# harp_audio_switch_v1_0.net
KiCad netlist of a schematic drawn in EAGLE
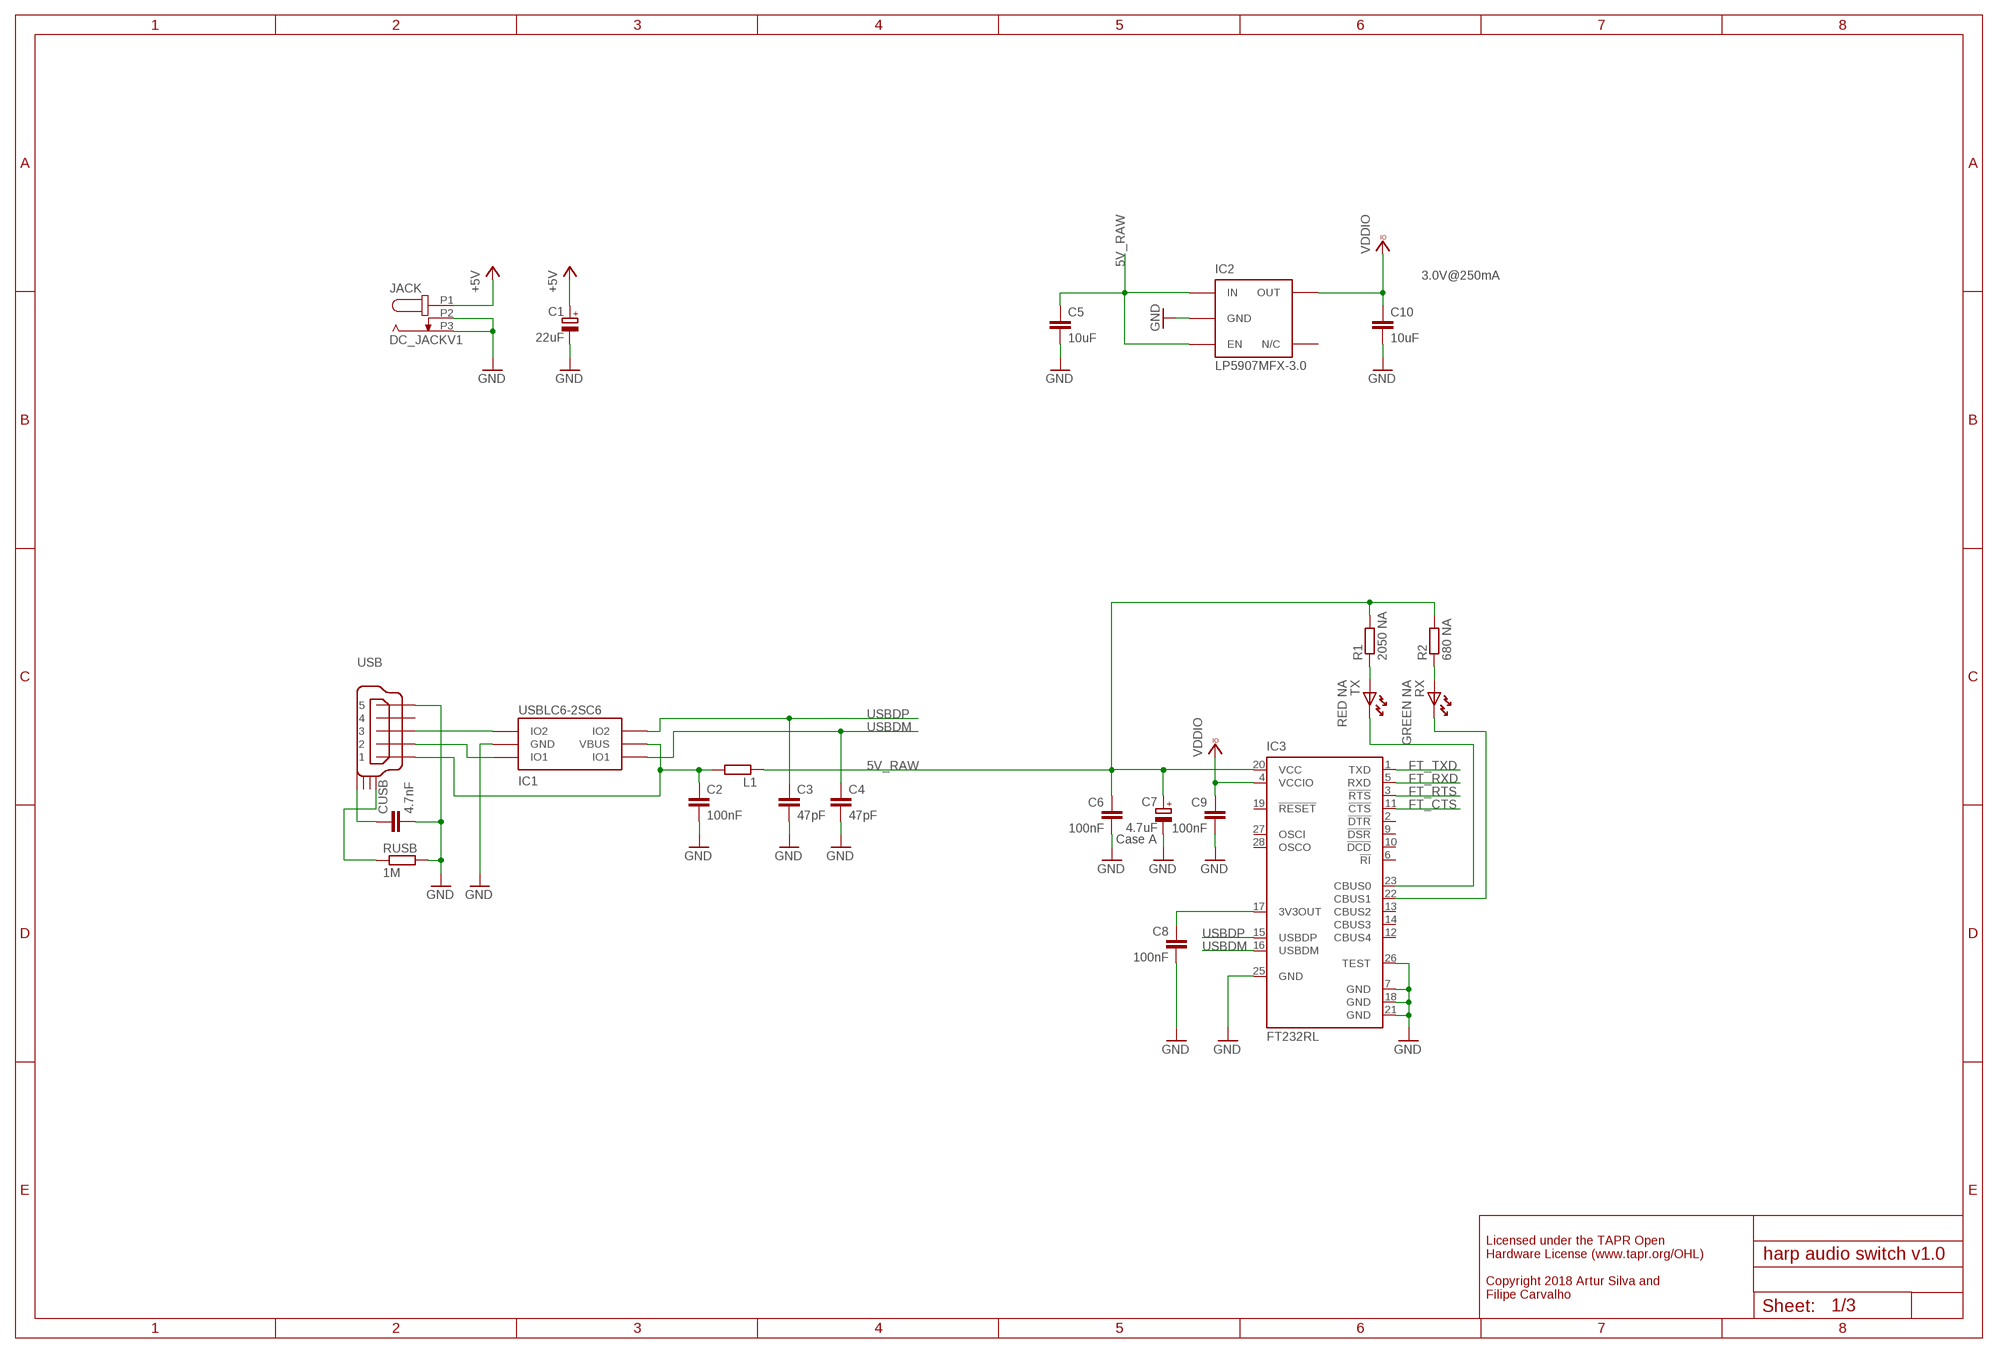
[diagram p0: schematic, sheet 1]
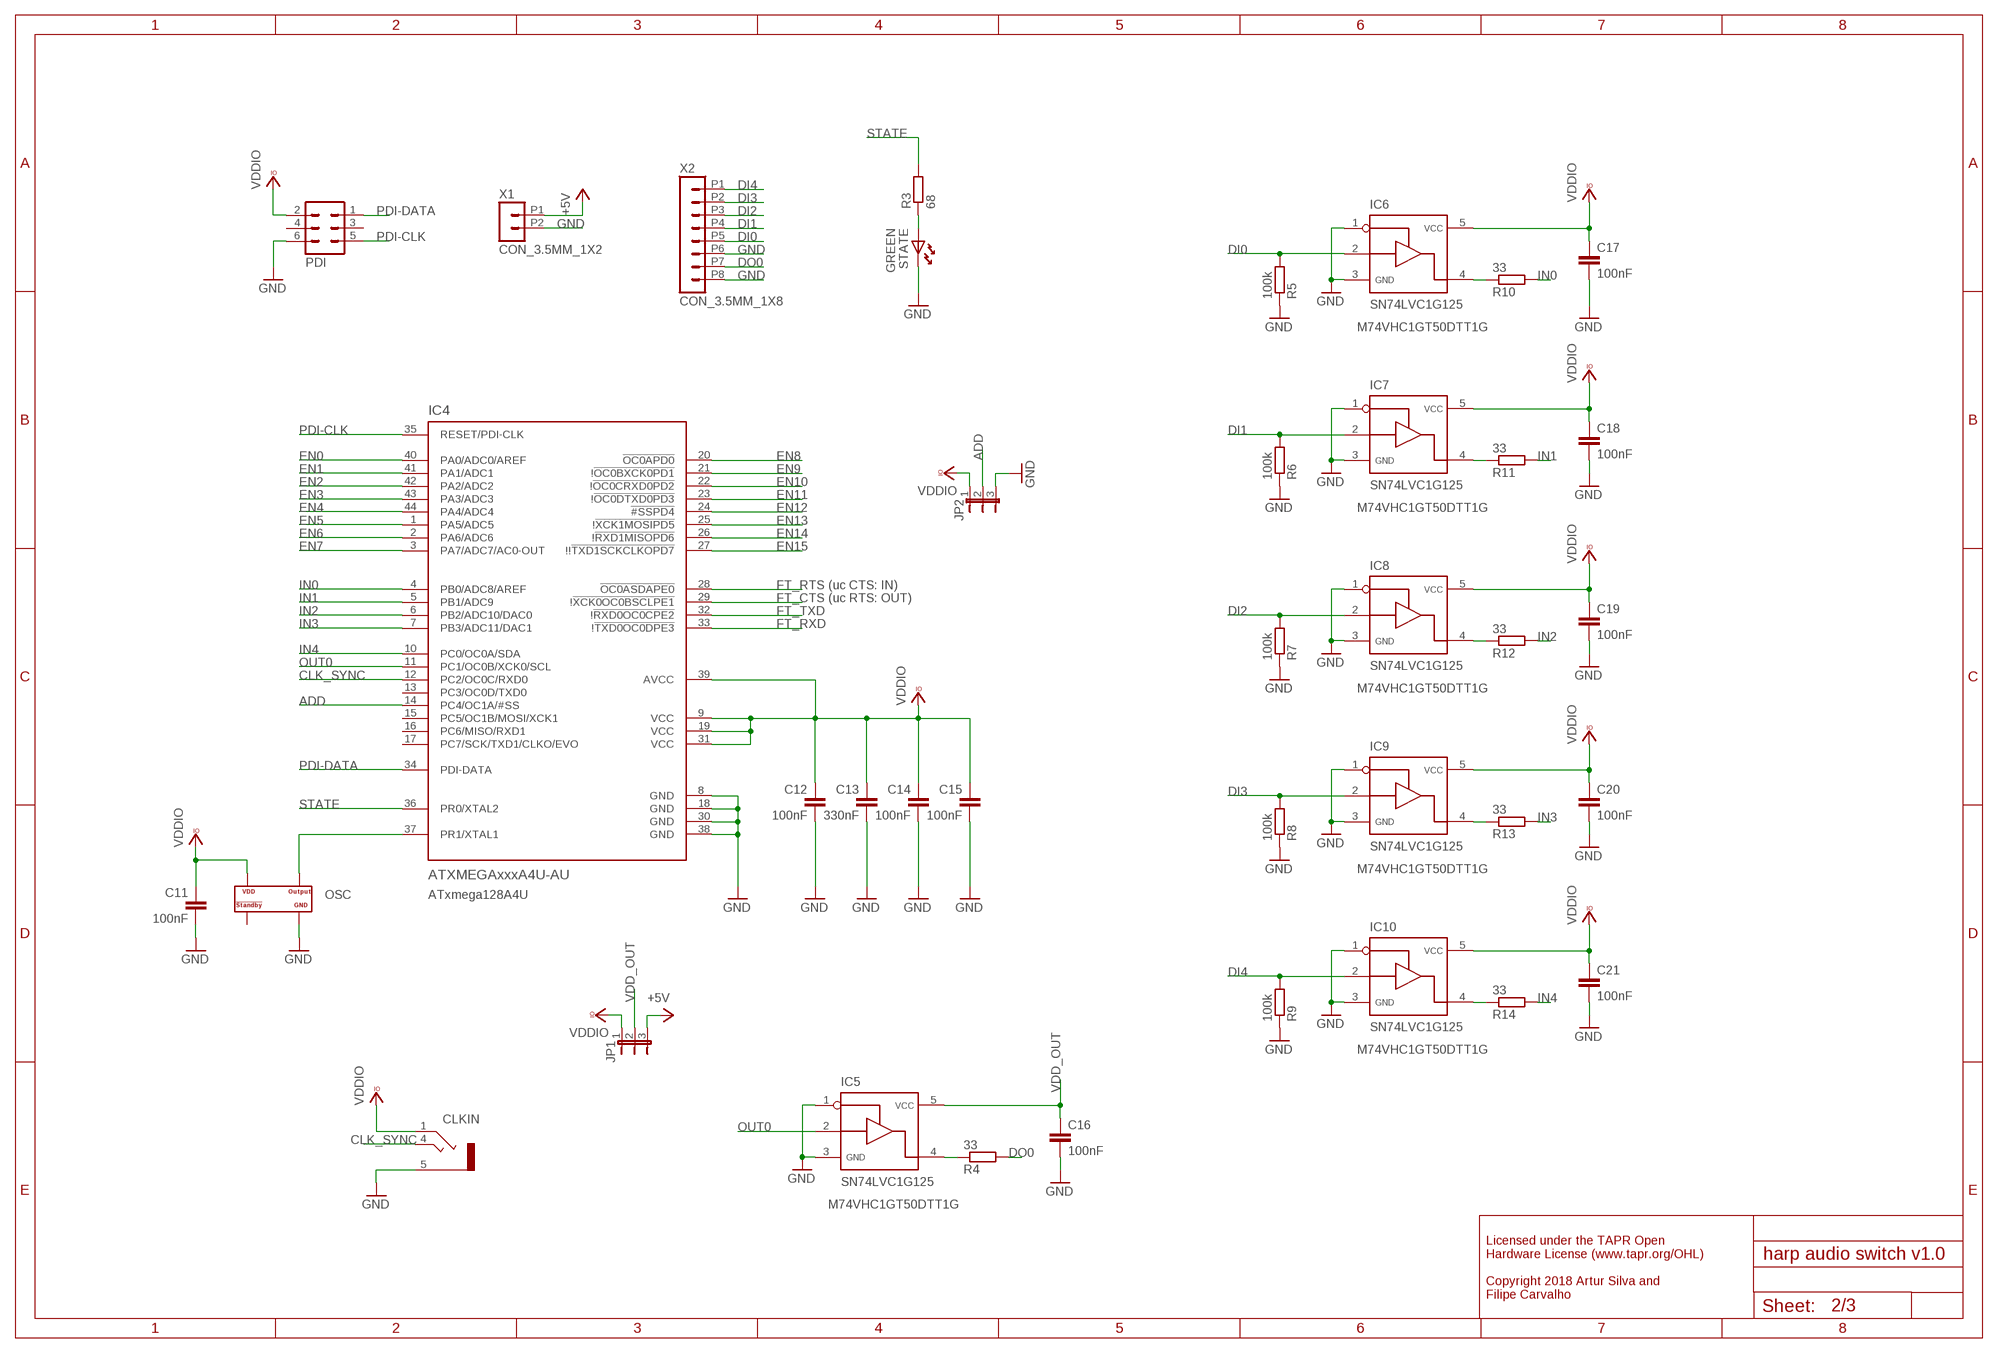
[diagram p1: schematic, sheet 2]
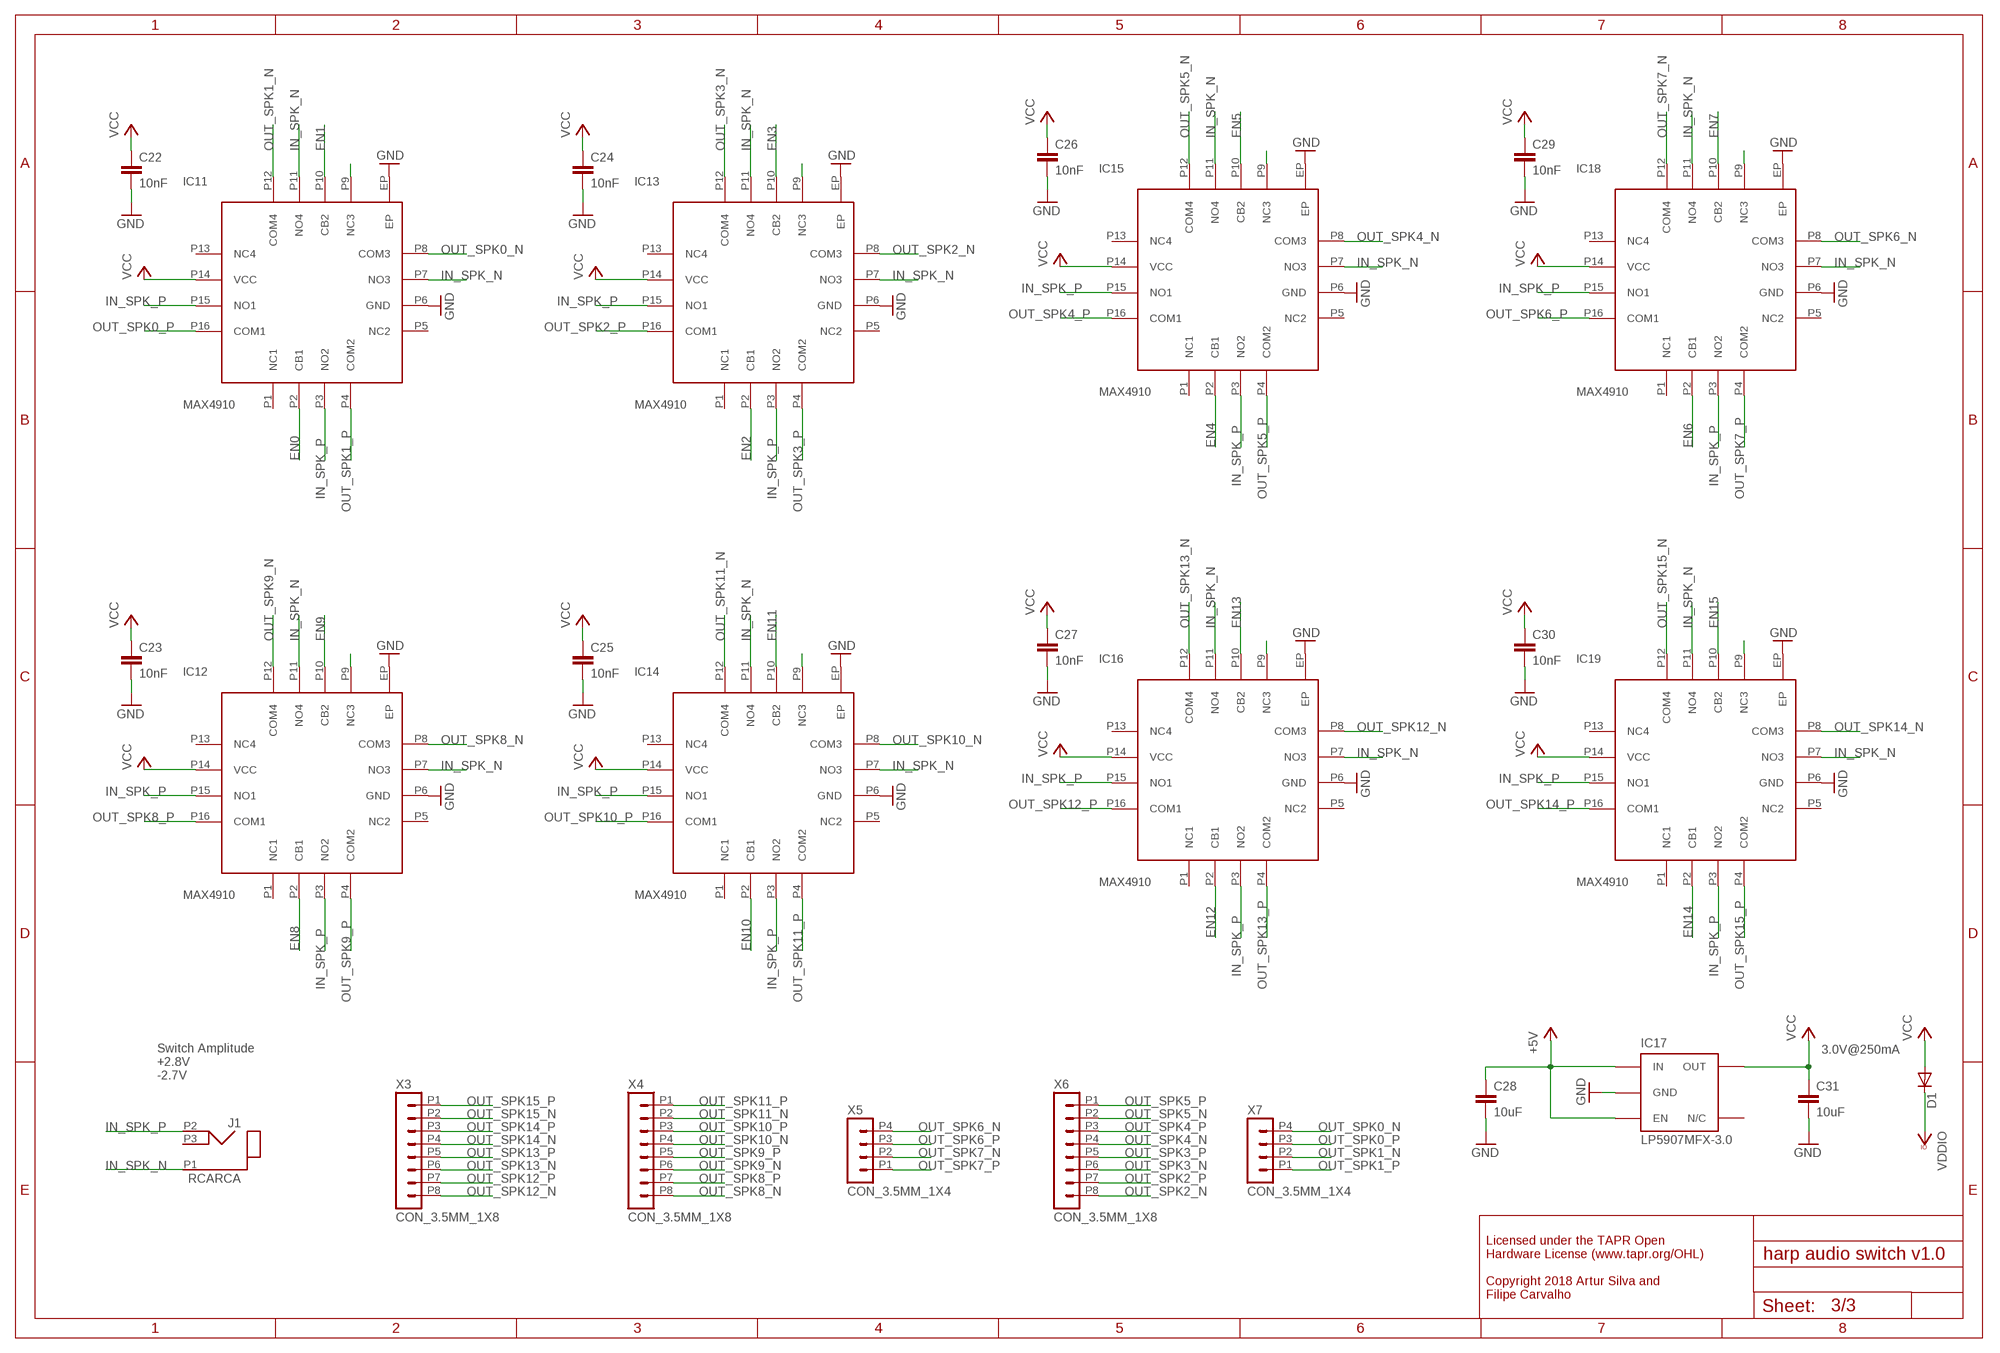
[diagram p2: schematic, sheet 3]

(export (version "E")
  (design (tool "Eeschema 10.0.6"))
  (components
    (comp (ref "C22")
      (value "10nF")
      (footprint "eagle-import:C0402")
      (libsource (lib "eagle-import") (part "C-EUC0402"))
    )
    (comp (ref "C23")
      (value "10nF")
      (footprint "eagle-import:C0402")
      (libsource (lib "eagle-import") (part "C-EUC0402"))
    )
    (comp (ref "C24")
      (value "10nF")
      (footprint "eagle-import:C0402")
      (libsource (lib "eagle-import") (part "C-EUC0402"))
    )
    (comp (ref "C25")
      (value "10nF")
      (footprint "eagle-import:C0402")
      (libsource (lib "eagle-import") (part "C-EUC0402"))
    )
    (comp (ref "C26")
      (value "10nF")
      (footprint "eagle-import:C0402")
      (libsource (lib "eagle-import") (part "C-EUC0402"))
    )
    (comp (ref "C27")
      (value "10nF")
      (footprint "eagle-import:C0402")
      (libsource (lib "eagle-import") (part "C-EUC0402"))
    )
    (comp (ref "C28")
      (value "10uF")
      (footprint "eagle-import:C0603")
      (libsource (lib "eagle-import") (part "C-EUC0603"))
    )
    (comp (ref "C29")
      (value "10nF")
      (footprint "eagle-import:C0402")
      (libsource (lib "eagle-import") (part "C-EUC0402"))
    )
    (comp (ref "C30")
      (value "10nF")
      (footprint "eagle-import:C0402")
      (libsource (lib "eagle-import") (part "C-EUC0402"))
    )
    (comp (ref "C31")
      (value "10uF")
      (footprint "eagle-import:C0603")
      (libsource (lib "eagle-import") (part "C-EUC0603"))
    )
    (comp (ref "D1")
      (value "DIODE-SOD323-R")
      (footprint "eagle-import:SOD323-R")
      (libsource (lib "eagle-import") (part "DIODE-SOD323-R"))
    )
    (comp (ref "IC11")
      (value "MAX4910")
      (footprint "eagle-import:QFN16")
      (libsource (lib "eagle-import") (part "MAX4910"))
    )
    (comp (ref "IC12")
      (value "MAX4910")
      (footprint "eagle-import:QFN16")
      (libsource (lib "eagle-import") (part "MAX4910"))
    )
    (comp (ref "IC13")
      (value "MAX4910")
      (footprint "eagle-import:QFN16")
      (libsource (lib "eagle-import") (part "MAX4910"))
    )
    (comp (ref "IC14")
      (value "MAX4910")
      (footprint "eagle-import:QFN16")
      (libsource (lib "eagle-import") (part "MAX4910"))
    )
    (comp (ref "IC15")
      (value "MAX4910")
      (footprint "eagle-import:QFN16")
      (libsource (lib "eagle-import") (part "MAX4910"))
    )
    (comp (ref "IC16")
      (value "MAX4910")
      (footprint "eagle-import:QFN16")
      (libsource (lib "eagle-import") (part "MAX4910"))
    )
    (comp (ref "IC17")
      (value "LP5907MFX-3.0")
      (footprint "eagle-import:TSOT23-5")
      (libsource (lib "eagle-import") (part "TLV700XX"))
    )
    (comp (ref "IC18")
      (value "MAX4910")
      (footprint "eagle-import:QFN16")
      (libsource (lib "eagle-import") (part "MAX4910"))
    )
    (comp (ref "IC19")
      (value "MAX4910")
      (footprint "eagle-import:QFN16")
      (libsource (lib "eagle-import") (part "MAX4910"))
    )
    (comp (ref "J1")
      (value "RCARCA")
      (footprint "eagle-import:RCA")
      (libsource (lib "eagle-import") (part "RCARCA"))
    )
    (comp (ref "X3")
      (value "CON_3.5MM_1X8")
      (footprint "eagle-import:CON_3.5MM_1X8")
      (libsource (lib "eagle-import") (part "CON_3.5MM_1X8"))
    )
    (comp (ref "X4")
      (value "CON_3.5MM_1X8")
      (footprint "eagle-import:CON_3.5MM_1X8")
      (libsource (lib "eagle-import") (part "CON_3.5MM_1X8"))
    )
    (comp (ref "X5")
      (value "CON_3.5MM_1X4")
      (footprint "eagle-import:CON_3.5MM_1X4")
      (libsource (lib "eagle-import") (part "CON_3.5MM_1X4"))
    )
    (comp (ref "X6")
      (value "CON_3.5MM_1X8")
      (footprint "eagle-import:CON_3.5MM_1X8")
      (libsource (lib "eagle-import") (part "CON_3.5MM_1X8"))
    )
    (comp (ref "X7")
      (value "CON_3.5MM_1X4")
      (footprint "eagle-import:CON_3.5MM_1X4")
      (libsource (lib "eagle-import") (part "CON_3.5MM_1X4"))
    )
    (comp (ref "C11")
      (value "100nF")
      (footprint "eagle-import:C0402")
      (libsource (lib "eagle-import") (part "C-EUC0402"))
    )
    (comp (ref "C12")
      (value "100nF")
      (footprint "eagle-import:C0402")
      (libsource (lib "eagle-import") (part "C-EUC0402"))
    )
    (comp (ref "C13")
      (value "330nF")
      (footprint "eagle-import:C0402")
      (libsource (lib "eagle-import") (part "C-EUC0402"))
    )
    (comp (ref "C14")
      (value "100nF")
      (footprint "eagle-import:C0402")
      (libsource (lib "eagle-import") (part "C-EUC0402"))
    )
    (comp (ref "C15")
      (value "100nF")
      (footprint "eagle-import:C0402")
      (libsource (lib "eagle-import") (part "C-EUC0402"))
    )
    (comp (ref "C16")
      (value "100nF")
      (footprint "eagle-import:C0402")
      (libsource (lib "eagle-import") (part "C-EUC0402"))
    )
    (comp (ref "C17")
      (value "100nF")
      (footprint "eagle-import:C0402")
      (libsource (lib "eagle-import") (part "C-EUC0402"))
    )
    (comp (ref "C18")
      (value "100nF")
      (footprint "eagle-import:C0402")
      (libsource (lib "eagle-import") (part "C-EUC0402"))
    )
    (comp (ref "C19")
      (value "100nF")
      (footprint "eagle-import:C0402")
      (libsource (lib "eagle-import") (part "C-EUC0402"))
    )
    (comp (ref "C20")
      (value "100nF")
      (footprint "eagle-import:C0402")
      (libsource (lib "eagle-import") (part "C-EUC0402"))
    )
    (comp (ref "C21")
      (value "100nF")
      (footprint "eagle-import:C0402")
      (libsource (lib "eagle-import") (part "C-EUC0402"))
    )
    (comp (ref "CLKIN")
      (value "STEREO_JACK")
      (footprint "eagle-import:35RASMT2BHNTRX")
      (libsource (lib "eagle-import") (part "STEREO_JACK"))
    )
    (comp (ref "IC4")
      (value "ATXMEGAxxxA4U-AU")
      (footprint "eagle-import:QFP80P1200X1200X120-44N")
      (libsource (lib "eagle-import") (part "AT-XMEGA-XXA4-AU"))
    )
    (comp (ref "IC5")
      (value "SN74LVC1G125")
      (footprint "eagle-import:SOT23-5")
      (libsource (lib "eagle-import") (part "SN74LVC1G125"))
    )
    (comp (ref "IC6")
      (value "SN74LVC1G125")
      (footprint "eagle-import:SOT23-5")
      (libsource (lib "eagle-import") (part "SN74LVC1G125"))
    )
    (comp (ref "IC7")
      (value "SN74LVC1G125")
      (footprint "eagle-import:SOT23-5")
      (libsource (lib "eagle-import") (part "SN74LVC1G125"))
    )
    (comp (ref "IC8")
      (value "SN74LVC1G125")
      (footprint "eagle-import:SOT23-5")
      (libsource (lib "eagle-import") (part "SN74LVC1G125"))
    )
    (comp (ref "IC9")
      (value "SN74LVC1G125")
      (footprint "eagle-import:SOT23-5")
      (libsource (lib "eagle-import") (part "SN74LVC1G125"))
    )
    (comp (ref "IC10")
      (value "SN74LVC1G125")
      (footprint "eagle-import:SOT23-5")
      (libsource (lib "eagle-import") (part "SN74LVC1G125"))
    )
    (comp (ref "JP1")
      (value "JP2E")
      (footprint "eagle-import:JP2")
      (libsource (lib "eagle-import") (part "JP2E"))
    )
    (comp (ref "JP2")
      (value "JP2E")
      (footprint "eagle-import:JP2")
      (libsource (lib "eagle-import") (part "JP2E"))
    )
    (comp (ref "OSC")
      (value "OSCILLATOR")
      (footprint "eagle-import:OSCILLATOR_3.2X2.5")
      (libsource (lib "eagle-import") (part "OSCILLATOR"))
    )
    (comp (ref "PDI")
      (value "MA03-2")
      (footprint "eagle-import:MA03-2")
      (libsource (lib "eagle-import") (part "MA03-2"))
    )
    (comp (ref "R3")
      (value "68")
      (footprint "eagle-import:R0402")
      (libsource (lib "eagle-import") (part "R-EU_R0402"))
    )
    (comp (ref "R4")
      (value "33")
      (footprint "eagle-import:R0402")
      (libsource (lib "eagle-import") (part "R-EU_R0402"))
    )
    (comp (ref "R5")
      (value "100k")
      (footprint "eagle-import:R0402")
      (libsource (lib "eagle-import") (part "R-EU_R0402"))
    )
    (comp (ref "R6")
      (value "100k")
      (footprint "eagle-import:R0402")
      (libsource (lib "eagle-import") (part "R-EU_R0402"))
    )
    (comp (ref "R7")
      (value "100k")
      (footprint "eagle-import:R0402")
      (libsource (lib "eagle-import") (part "R-EU_R0402"))
    )
    (comp (ref "R8")
      (value "100k")
      (footprint "eagle-import:R0402")
      (libsource (lib "eagle-import") (part "R-EU_R0402"))
    )
    (comp (ref "R9")
      (value "100k")
      (footprint "eagle-import:R0402")
      (libsource (lib "eagle-import") (part "R-EU_R0402"))
    )
    (comp (ref "R10")
      (value "33")
      (footprint "eagle-import:R0402")
      (libsource (lib "eagle-import") (part "R-EU_R0402"))
    )
    (comp (ref "R11")
      (value "33")
      (footprint "eagle-import:R0402")
      (libsource (lib "eagle-import") (part "R-EU_R0402"))
    )
    (comp (ref "R12")
      (value "33")
      (footprint "eagle-import:R0402")
      (libsource (lib "eagle-import") (part "R-EU_R0402"))
    )
    (comp (ref "R13")
      (value "33")
      (footprint "eagle-import:R0402")
      (libsource (lib "eagle-import") (part "R-EU_R0402"))
    )
    (comp (ref "R14")
      (value "33")
      (footprint "eagle-import:R0402")
      (libsource (lib "eagle-import") (part "R-EU_R0402"))
    )
    (comp (ref "STATE")
      (value "GREEN")
      (footprint "eagle-import:LED_HAND")
      (libsource (lib "eagle-import") (part "LEDHAND"))
    )
    (comp (ref "X1")
      (value "CON_3.5MM_1X2")
      (footprint "eagle-import:CON_3.5MM_1X2")
      (libsource (lib "eagle-import") (part "CON_3.5MM_1X2"))
    )
    (comp (ref "X2")
      (value "CON_3.5MM_1X8")
      (footprint "eagle-import:CON_3.5MM_1X8")
      (libsource (lib "eagle-import") (part "CON_3.5MM_1X8"))
    )
    (comp (ref "C1")
      (value "22uF")
      (footprint "eagle-import:CAP_100UF_HAND")
      (libsource (lib "eagle-import") (part "CAP_100UFHAND"))
    )
    (comp (ref "C2")
      (value "100nF")
      (footprint "eagle-import:C0402")
      (libsource (lib "eagle-import") (part "C-EUC0402"))
    )
    (comp (ref "C3")
      (value "47pF")
      (footprint "eagle-import:C0402")
      (libsource (lib "eagle-import") (part "C-EUC0402"))
    )
    (comp (ref "C4")
      (value "47pF")
      (footprint "eagle-import:C0402")
      (libsource (lib "eagle-import") (part "C-EUC0402"))
    )
    (comp (ref "C5")
      (value "10uF")
      (footprint "eagle-import:C0603")
      (libsource (lib "eagle-import") (part "C-EUC0603"))
    )
    (comp (ref "C6")
      (value "100nF")
      (footprint "eagle-import:C0402")
      (libsource (lib "eagle-import") (part "C-EUC0402"))
    )
    (comp (ref "C7")
      (value "4.7uF")
      (footprint "eagle-import:A_3216-18W")
      (libsource (lib "eagle-import") (part "CPOL-EUA/3216-18W"))
    )
    (comp (ref "C8")
      (value "100nF")
      (footprint "eagle-import:C0402")
      (libsource (lib "eagle-import") (part "C-EUC0402"))
    )
    (comp (ref "C9")
      (value "100nF")
      (footprint "eagle-import:C0402")
      (libsource (lib "eagle-import") (part "C-EUC0402"))
    )
    (comp (ref "C10")
      (value "10uF")
      (footprint "eagle-import:C0603")
      (libsource (lib "eagle-import") (part "C-EUC0603"))
    )
    (comp (ref "CUSB")
      (value "4.7nF")
      (footprint "eagle-import:C0402")
      (libsource (lib "eagle-import") (part "C-EUC0402"))
    )
    (comp (ref "IC1")
      (value "USBLC6-2SC6")
      (footprint "eagle-import:SOT23-6L")
      (libsource (lib "eagle-import") (part "USBLC6-2"))
    )
    (comp (ref "IC2")
      (value "LP5907MFX-3.0")
      (footprint "eagle-import:TSOT23-5")
      (libsource (lib "eagle-import") (part "TLV700XX"))
    )
    (comp (ref "IC3")
      (value "FT232RL")
      (footprint "eagle-import:SSOP28")
      (libsource (lib "eagle-import") (part "FT232RL"))
    )
    (comp (ref "JACK")
      (value "DC_JACKV1")
      (footprint "eagle-import:DC_POWER_INPUT")
      (libsource (lib "eagle-import") (part "DC_JACKV1"))
    )
    (comp (ref "L1")
      (value "???")
      (footprint "eagle-import:R0805")
      (libsource (lib "eagle-import") (part "R-EU_R0805"))
    )
    (comp (ref "R1")
      (value "2050 NA")
      (footprint "eagle-import:R0402")
      (libsource (lib "eagle-import") (part "R-EU_R0402"))
    )
    (comp (ref "R2")
      (value "680 NA")
      (footprint "eagle-import:R0402")
      (libsource (lib "eagle-import") (part "R-EU_R0402"))
    )
    (comp (ref "RUSB")
      (value "1M")
      (footprint "eagle-import:R0402")
      (libsource (lib "eagle-import") (part "R-EU_R0402"))
    )
    (comp (ref "RX")
      (value "GREEN NA")
      (footprint "eagle-import:LED_HAND")
      (libsource (lib "eagle-import") (part "LEDHAND"))
    )
    (comp (ref "TX")
      (value "RED NA")
      (footprint "eagle-import:LED_HAND")
      (libsource (lib "eagle-import") (part "LEDHAND"))
    )
    (comp (ref "USB")
      (value "USB_MINI_B")
      (footprint "eagle-import:240-0002-1")
      (libsource (lib "eagle-import") (part "USB_MINI_B"))
    )
  )
  (nets
    (net (code "1") (name "+5V") (class "Default")
      (node (ref "C1") (pin "+") (pinfunction "+_+") (pintype "passive"))
      (node (ref "C28") (pin "1") (pinfunction "1_1") (pintype "passive"))
      (node (ref "IC17") (pin "1") (pinfunction "IN_1") (pintype "bidirectional"))
      (node (ref "IC17") (pin "3") (pinfunction "EN_3") (pintype "bidirectional"))
      (node (ref "JACK") (pin "P1") (pinfunction "1_P1") (pintype "passive"))
      (node (ref "JP1") (pin "3") (pinfunction "3_3") (pintype "passive"))
      (node (ref "X1") (pin "P1") (pinfunction "1_P1") (pintype "passive"))
    )
    (net (code "2") (name "5V_RAW") (class "Default")
      (node (ref "C5") (pin "1") (pinfunction "1_1") (pintype "passive"))
      (node (ref "C6") (pin "1") (pinfunction "1_1") (pintype "passive"))
      (node (ref "C7") (pin "+") (pinfunction "+_+") (pintype "passive"))
      (node (ref "IC2") (pin "1") (pinfunction "IN_1") (pintype "bidirectional"))
      (node (ref "IC2") (pin "3") (pinfunction "EN_3") (pintype "bidirectional"))
      (node (ref "IC3") (pin "20") (pinfunction "VCC_20") (pintype "power_in"))
      (node (ref "L1") (pin "1") (pinfunction "1_1") (pintype "passive"))
      (node (ref "R1") (pin "2") (pinfunction "2_2") (pintype "passive"))
      (node (ref "R2") (pin "2") (pinfunction "2_2") (pintype "passive"))
    )
    (net (code "3") (name "ADD") (class "Default")
      (node (ref "IC4") (pin "14") (pinfunction "PC4/OC1A/#SS_14") (pintype "bidirectional"))
      (node (ref "JP2") (pin "2") (pinfunction "2_2") (pintype "passive"))
    )
    (net (code "4") (name "CLK_SYNC") (class "Default")
      (node (ref "CLKIN") (pin "4") (pinfunction "4_4") (pintype "passive"))
      (node (ref "IC4") (pin "12") (pinfunction "PC2/OC0C/RXD0_12") (pintype "bidirectional"))
    )
    (net (code "5") (name "DI0") (class "Default")
      (node (ref "IC6") (pin "2") (pinfunction "P$2_2") (pintype "bidirectional"))
      (node (ref "R5") (pin "2") (pinfunction "2_2") (pintype "passive"))
      (node (ref "X2") (pin "P5") (pinfunction "5_P5") (pintype "passive"))
    )
    (net (code "6") (name "DI1") (class "Default")
      (node (ref "IC7") (pin "2") (pinfunction "P$2_2") (pintype "bidirectional"))
      (node (ref "R6") (pin "2") (pinfunction "2_2") (pintype "passive"))
      (node (ref "X2") (pin "P4") (pinfunction "4_P4") (pintype "passive"))
    )
    (net (code "7") (name "DI2") (class "Default")
      (node (ref "IC8") (pin "2") (pinfunction "P$2_2") (pintype "bidirectional"))
      (node (ref "R7") (pin "2") (pinfunction "2_2") (pintype "passive"))
      (node (ref "X2") (pin "P3") (pinfunction "3_P3") (pintype "passive"))
    )
    (net (code "8") (name "DI3") (class "Default")
      (node (ref "IC9") (pin "2") (pinfunction "P$2_2") (pintype "bidirectional"))
      (node (ref "R8") (pin "2") (pinfunction "2_2") (pintype "passive"))
      (node (ref "X2") (pin "P2") (pinfunction "2_P2") (pintype "passive"))
    )
    (net (code "9") (name "DI4") (class "Default")
      (node (ref "IC10") (pin "2") (pinfunction "P$2_2") (pintype "bidirectional"))
      (node (ref "R9") (pin "2") (pinfunction "2_2") (pintype "passive"))
      (node (ref "X2") (pin "P1") (pinfunction "1_P1") (pintype "passive"))
    )
    (net (code "10") (name "DO0") (class "Default")
      (node (ref "R4") (pin "2") (pinfunction "2_2") (pintype "passive"))
      (node (ref "X2") (pin "P7") (pinfunction "7_P7") (pintype "passive"))
    )
    (net (code "11") (name "EN0") (class "Default")
      (node (ref "IC11") (pin "P2") (pinfunction "CB1_P2") (pintype "bidirectional"))
      (node (ref "IC4") (pin "40") (pinfunction "PA0/ADC0/AREF_40") (pintype "bidirectional"))
    )
    (net (code "12") (name "EN1") (class "Default")
      (node (ref "IC11") (pin "P10") (pinfunction "CB2_P10") (pintype "power_in"))
      (node (ref "IC4") (pin "41") (pinfunction "PA1/ADC1_41") (pintype "bidirectional"))
    )
    (net (code "13") (name "EN2") (class "Default")
      (node (ref "IC13") (pin "P2") (pinfunction "CB1_P2") (pintype "bidirectional"))
      (node (ref "IC4") (pin "42") (pinfunction "PA2/ADC2_42") (pintype "bidirectional"))
    )
    (net (code "14") (name "EN3") (class "Default")
      (node (ref "IC13") (pin "P10") (pinfunction "CB2_P10") (pintype "power_in"))
      (node (ref "IC4") (pin "43") (pinfunction "PA3/ADC3_43") (pintype "bidirectional"))
    )
    (net (code "15") (name "EN4") (class "Default")
      (node (ref "IC15") (pin "P2") (pinfunction "CB1_P2") (pintype "bidirectional"))
      (node (ref "IC4") (pin "44") (pinfunction "PA4/ADC4_44") (pintype "bidirectional"))
    )
    (net (code "16") (name "EN5") (class "Default")
      (node (ref "IC15") (pin "P10") (pinfunction "CB2_P10") (pintype "power_in"))
      (node (ref "IC4") (pin "1") (pinfunction "PA5/ADC5_1") (pintype "bidirectional"))
    )
    (net (code "17") (name "EN6") (class "Default")
      (node (ref "IC18") (pin "P2") (pinfunction "CB1_P2") (pintype "bidirectional"))
      (node (ref "IC4") (pin "2") (pinfunction "PA6/ADC6_2") (pintype "bidirectional"))
    )
    (net (code "18") (name "EN7") (class "Default")
      (node (ref "IC18") (pin "P10") (pinfunction "CB2_P10") (pintype "power_in"))
      (node (ref "IC4") (pin "3") (pinfunction "PA7/ADC7/AC0-OUT_3") (pintype "bidirectional"))
    )
    (net (code "19") (name "EN8") (class "Default")
      (node (ref "IC12") (pin "P2") (pinfunction "CB1_P2") (pintype "bidirectional"))
      (node (ref "IC4") (pin "20") (pinfunction "~{OC0APD0}_20") (pintype "bidirectional"))
    )
    (net (code "20") (name "EN9") (class "Default")
      (node (ref "IC12") (pin "P10") (pinfunction "CB2_P10") (pintype "power_in"))
      (node (ref "IC4") (pin "21") (pinfunction "~OC0BXCK0PD1_21") (pintype "bidirectional"))
    )
    (net (code "21") (name "EN10") (class "Default")
      (node (ref "IC14") (pin "P2") (pinfunction "CB1_P2") (pintype "bidirectional"))
      (node (ref "IC4") (pin "22") (pinfunction "~OC0CRXD0PD2_22") (pintype "bidirectional"))
    )
    (net (code "22") (name "EN11") (class "Default")
      (node (ref "IC14") (pin "P10") (pinfunction "CB2_P10") (pintype "power_in"))
      (node (ref "IC4") (pin "23") (pinfunction "~OC0DTXD0PD3_23") (pintype "bidirectional"))
    )
    (net (code "23") (name "EN12") (class "Default")
      (node (ref "IC16") (pin "P2") (pinfunction "CB1_P2") (pintype "bidirectional"))
      (node (ref "IC4") (pin "24") (pinfunction "~{#SSPD4}_24") (pintype "bidirectional"))
    )
    (net (code "24") (name "EN13") (class "Default")
      (node (ref "IC16") (pin "P10") (pinfunction "CB2_P10") (pintype "power_in"))
      (node (ref "IC4") (pin "25") (pinfunction "~XCK1MOSIPD5_25") (pintype "bidirectional"))
    )
    (net (code "25") (name "EN14") (class "Default")
      (node (ref "IC19") (pin "P2") (pinfunction "CB1_P2") (pintype "bidirectional"))
      (node (ref "IC4") (pin "26") (pinfunction "~RXD1MISOPD6_26") (pintype "bidirectional"))
    )
    (net (code "26") (name "EN15") (class "Default")
      (node (ref "IC19") (pin "P10") (pinfunction "CB2_P10") (pintype "power_in"))
      (node (ref "IC4") (pin "27") (pinfunction "~~{TXD1SCKCLKOPD7}_27") (pintype "bidirectional"))
    )
    (net (code "27") (name "FT_CTS") (class "Default")
      (node (ref "IC3") (pin "11") (pinfunction "~{CTS}_11") (pintype "input"))
      (node (ref "IC4") (pin "29") (pinfunction "~XCK0OC0BSCLPE1_29") (pintype "bidirectional"))
    )
    (net (code "28") (name "FT_RTS") (class "Default")
      (node (ref "IC3") (pin "3") (pinfunction "~{RTS}_3") (pintype "output"))
      (node (ref "IC4") (pin "28") (pinfunction "~{OC0ASDAPE0}_28") (pintype "bidirectional"))
    )
    (net (code "29") (name "FT_RXD") (class "Default")
      (node (ref "IC3") (pin "5") (pinfunction "RXD_5") (pintype "input"))
      (node (ref "IC4") (pin "33") (pinfunction "~TXD0OC0DPE3_33") (pintype "bidirectional"))
    )
    (net (code "30") (name "FT_TXD") (class "Default")
      (node (ref "IC3") (pin "1") (pinfunction "TXD_1") (pintype "output"))
      (node (ref "IC4") (pin "32") (pinfunction "~RXD0OC0CPE2_32") (pintype "bidirectional"))
    )
    (net (code "31") (name "GND") (class "Default")
      (node (ref "C1") (pin "-") (pinfunction "-_-") (pintype "passive"))
      (node (ref "C10") (pin "2") (pinfunction "2_2") (pintype "passive"))
      (node (ref "C11") (pin "2") (pinfunction "2_2") (pintype "passive"))
      (node (ref "C12") (pin "2") (pinfunction "2_2") (pintype "passive"))
      (node (ref "C13") (pin "2") (pinfunction "2_2") (pintype "passive"))
      (node (ref "C14") (pin "2") (pinfunction "2_2") (pintype "passive"))
      (node (ref "C15") (pin "2") (pinfunction "2_2") (pintype "passive"))
      (node (ref "C16") (pin "2") (pinfunction "2_2") (pintype "passive"))
      (node (ref "C17") (pin "2") (pinfunction "2_2") (pintype "passive"))
      (node (ref "C18") (pin "2") (pinfunction "2_2") (pintype "passive"))
      (node (ref "C19") (pin "2") (pinfunction "2_2") (pintype "passive"))
      (node (ref "C2") (pin "2") (pinfunction "2_2") (pintype "passive"))
      (node (ref "C20") (pin "2") (pinfunction "2_2") (pintype "passive"))
      (node (ref "C21") (pin "2") (pinfunction "2_2") (pintype "passive"))
      (node (ref "C22") (pin "2") (pinfunction "2_2") (pintype "passive"))
      (node (ref "C23") (pin "2") (pinfunction "2_2") (pintype "passive"))
      (node (ref "C24") (pin "2") (pinfunction "2_2") (pintype "passive"))
      (node (ref "C25") (pin "2") (pinfunction "2_2") (pintype "passive"))
      (node (ref "C26") (pin "2") (pinfunction "2_2") (pintype "passive"))
      (node (ref "C27") (pin "2") (pinfunction "2_2") (pintype "passive"))
      (node (ref "C28") (pin "2") (pinfunction "2_2") (pintype "passive"))
      (node (ref "C29") (pin "2") (pinfunction "2_2") (pintype "passive"))
      (node (ref "C3") (pin "2") (pinfunction "2_2") (pintype "passive"))
      (node (ref "C30") (pin "2") (pinfunction "2_2") (pintype "passive"))
      (node (ref "C31") (pin "2") (pinfunction "2_2") (pintype "passive"))
      (node (ref "C4") (pin "2") (pinfunction "2_2") (pintype "passive"))
      (node (ref "C5") (pin "2") (pinfunction "2_2") (pintype "passive"))
      (node (ref "C6") (pin "2") (pinfunction "2_2") (pintype "passive"))
      (node (ref "C7") (pin "-") (pinfunction "-_-") (pintype "passive"))
      (node (ref "C8") (pin "2") (pinfunction "2_2") (pintype "passive"))
      (node (ref "C9") (pin "2") (pinfunction "2_2") (pintype "passive"))
      (node (ref "CLKIN") (pin "5") (pinfunction "5_5") (pintype "passive"))
      (node (ref "CUSB") (pin "2") (pinfunction "2_2") (pintype "passive"))
      (node (ref "IC1") (pin "P$2") (pinfunction "GND_P$2") (pintype "bidirectional"))
      (node (ref "IC10") (pin "1") (pinfunction "P$1_1") (pintype "bidirectional"))
      (node (ref "IC10") (pin "3") (pinfunction "P$3_3") (pintype "bidirectional"))
      (node (ref "IC11") (pin "EP") (pinfunction "EP_EP") (pintype "bidirectional"))
      (node (ref "IC11") (pin "P6") (pinfunction "GND_P6") (pintype "bidirectional"))
      (node (ref "IC12") (pin "EP") (pinfunction "EP_EP") (pintype "bidirectional"))
      (node (ref "IC12") (pin "P6") (pinfunction "GND_P6") (pintype "bidirectional"))
      (node (ref "IC13") (pin "EP") (pinfunction "EP_EP") (pintype "bidirectional"))
      (node (ref "IC13") (pin "P6") (pinfunction "GND_P6") (pintype "bidirectional"))
      (node (ref "IC14") (pin "EP") (pinfunction "EP_EP") (pintype "bidirectional"))
      (node (ref "IC14") (pin "P6") (pinfunction "GND_P6") (pintype "bidirectional"))
      (node (ref "IC15") (pin "EP") (pinfunction "EP_EP") (pintype "bidirectional"))
      (node (ref "IC15") (pin "P6") (pinfunction "GND_P6") (pintype "bidirectional"))
      (node (ref "IC16") (pin "EP") (pinfunction "EP_EP") (pintype "bidirectional"))
      (node (ref "IC16") (pin "P6") (pinfunction "GND_P6") (pintype "bidirectional"))
      (node (ref "IC17") (pin "2") (pinfunction "GND_2") (pintype "bidirectional"))
      (node (ref "IC18") (pin "EP") (pinfunction "EP_EP") (pintype "bidirectional"))
      (node (ref "IC18") (pin "P6") (pinfunction "GND_P6") (pintype "bidirectional"))
      (node (ref "IC19") (pin "EP") (pinfunction "EP_EP") (pintype "bidirectional"))
      (node (ref "IC19") (pin "P6") (pinfunction "GND_P6") (pintype "bidirectional"))
      (node (ref "IC2") (pin "2") (pinfunction "GND_2") (pintype "bidirectional"))
      (node (ref "IC3") (pin "18") (pinfunction "GND_18") (pintype "power_in"))
      (node (ref "IC3") (pin "21") (pinfunction "GND_21") (pintype "power_in"))
      (node (ref "IC3") (pin "25") (pinfunction "GND_25") (pintype "power_in"))
      (node (ref "IC3") (pin "26") (pinfunction "TEST_26") (pintype "input"))
      (node (ref "IC3") (pin "7") (pinfunction "GND_7") (pintype "power_in"))
      (node (ref "IC4") (pin "18") (pinfunction "GND_18") (pintype "power_in"))
      (node (ref "IC4") (pin "30") (pinfunction "GND_30") (pintype "power_in"))
      (node (ref "IC4") (pin "38") (pinfunction "GND_38") (pintype "power_in"))
      (node (ref "IC4") (pin "8") (pinfunction "GND_8") (pintype "power_in"))
      (node (ref "IC5") (pin "1") (pinfunction "P$1_1") (pintype "bidirectional"))
      (node (ref "IC5") (pin "3") (pinfunction "P$3_3") (pintype "bidirectional"))
      (node (ref "IC6") (pin "1") (pinfunction "P$1_1") (pintype "bidirectional"))
      (node (ref "IC6") (pin "3") (pinfunction "P$3_3") (pintype "bidirectional"))
      (node (ref "IC7") (pin "1") (pinfunction "P$1_1") (pintype "bidirectional"))
      (node (ref "IC7") (pin "3") (pinfunction "P$3_3") (pintype "bidirectional"))
      (node (ref "IC8") (pin "1") (pinfunction "P$1_1") (pintype "bidirectional"))
      (node (ref "IC8") (pin "3") (pinfunction "P$3_3") (pintype "bidirectional"))
      (node (ref "IC9") (pin "1") (pinfunction "P$1_1") (pintype "bidirectional"))
      (node (ref "IC9") (pin "3") (pinfunction "P$3_3") (pintype "bidirectional"))
      (node (ref "JACK") (pin "P2") (pinfunction "2_P2") (pintype "passive"))
      (node (ref "JACK") (pin "P3") (pinfunction "3_P3") (pintype "passive"))
      (node (ref "JP2") (pin "3") (pinfunction "3_3") (pintype "passive"))
      (node (ref "OSC") (pin "P$2") (pinfunction "GND_P$2") (pintype "passive"))
      (node (ref "PDI") (pin "6") (pinfunction "6_6") (pintype "passive"))
      (node (ref "R5") (pin "1") (pinfunction "1_1") (pintype "passive"))
      (node (ref "R6") (pin "1") (pinfunction "1_1") (pintype "passive"))
      (node (ref "R7") (pin "1") (pinfunction "1_1") (pintype "passive"))
      (node (ref "R8") (pin "1") (pinfunction "1_1") (pintype "passive"))
      (node (ref "R9") (pin "1") (pinfunction "1_1") (pintype "passive"))
      (node (ref "RUSB") (pin "2") (pinfunction "2_2") (pintype "passive"))
      (node (ref "STATE") (pin "K") (pinfunction "K_K") (pintype "bidirectional"))
      (node (ref "USB") (pin "P$5") (pinfunction "5_P$5") (pintype "bidirectional"))
      (node (ref "X1") (pin "P2") (pinfunction "2_P2") (pintype "passive"))
      (node (ref "X2") (pin "P6") (pinfunction "6_P6") (pintype "passive"))
      (node (ref "X2") (pin "P8") (pinfunction "8_P8") (pintype "passive"))
    )
    (net (code "32") (name "IN0") (class "Default")
      (node (ref "IC4") (pin "4") (pinfunction "PB0/ADC8/AREF_4") (pintype "bidirectional"))
      (node (ref "R10") (pin "2") (pinfunction "2_2") (pintype "passive"))
    )
    (net (code "33") (name "IN1") (class "Default")
      (node (ref "IC4") (pin "5") (pinfunction "PB1/ADC9_5") (pintype "bidirectional"))
      (node (ref "R11") (pin "2") (pinfunction "2_2") (pintype "passive"))
    )
    (net (code "34") (name "IN2") (class "Default")
      (node (ref "IC4") (pin "6") (pinfunction "PB2/ADC10/DAC0_6") (pintype "bidirectional"))
      (node (ref "R12") (pin "2") (pinfunction "2_2") (pintype "passive"))
    )
    (net (code "35") (name "IN3") (class "Default")
      (node (ref "IC4") (pin "7") (pinfunction "PB3/ADC11/DAC1_7") (pintype "bidirectional"))
      (node (ref "R13") (pin "2") (pinfunction "2_2") (pintype "passive"))
    )
    (net (code "36") (name "IN4") (class "Default")
      (node (ref "IC4") (pin "10") (pinfunction "PC0/OC0A/SDA_10") (pintype "bidirectional"))
      (node (ref "R14") (pin "2") (pinfunction "2_2") (pintype "passive"))
    )
    (net (code "37") (name "IN_SPK_N") (class "Default")
      (node (ref "IC11") (pin "P11") (pinfunction "NO4_P11") (pintype "bidirectional"))
      (node (ref "IC11") (pin "P7") (pinfunction "NO3_P7") (pintype "bidirectional"))
      (node (ref "IC12") (pin "P11") (pinfunction "NO4_P11") (pintype "bidirectional"))
      (node (ref "IC12") (pin "P7") (pinfunction "NO3_P7") (pintype "bidirectional"))
      (node (ref "IC13") (pin "P11") (pinfunction "NO4_P11") (pintype "bidirectional"))
      (node (ref "IC13") (pin "P7") (pinfunction "NO3_P7") (pintype "bidirectional"))
      (node (ref "IC14") (pin "P11") (pinfunction "NO4_P11") (pintype "bidirectional"))
      (node (ref "IC14") (pin "P7") (pinfunction "NO3_P7") (pintype "bidirectional"))
      (node (ref "IC15") (pin "P11") (pinfunction "NO4_P11") (pintype "bidirectional"))
      (node (ref "IC15") (pin "P7") (pinfunction "NO3_P7") (pintype "bidirectional"))
      (node (ref "IC16") (pin "P11") (pinfunction "NO4_P11") (pintype "bidirectional"))
      (node (ref "IC16") (pin "P7") (pinfunction "NO3_P7") (pintype "bidirectional"))
      (node (ref "IC18") (pin "P11") (pinfunction "NO4_P11") (pintype "bidirectional"))
      (node (ref "IC18") (pin "P7") (pinfunction "NO3_P7") (pintype "bidirectional"))
      (node (ref "IC19") (pin "P11") (pinfunction "NO4_P11") (pintype "bidirectional"))
      (node (ref "IC19") (pin "P7") (pinfunction "NO3_P7") (pintype "bidirectional"))
      (node (ref "J1") (pin "P1") (pinfunction "1_P1") (pintype "passive"))
    )
    (net (code "38") (name "IN_SPK_P") (class "Default")
      (node (ref "IC11") (pin "P15") (pinfunction "NO1_P15") (pintype "bidirectional"))
      (node (ref "IC11") (pin "P3") (pinfunction "NO2_P3") (pintype "bidirectional"))
      (node (ref "IC12") (pin "P15") (pinfunction "NO1_P15") (pintype "bidirectional"))
      (node (ref "IC12") (pin "P3") (pinfunction "NO2_P3") (pintype "bidirectional"))
      (node (ref "IC13") (pin "P15") (pinfunction "NO1_P15") (pintype "bidirectional"))
      (node (ref "IC13") (pin "P3") (pinfunction "NO2_P3") (pintype "bidirectional"))
      (node (ref "IC14") (pin "P15") (pinfunction "NO1_P15") (pintype "bidirectional"))
      (node (ref "IC14") (pin "P3") (pinfunction "NO2_P3") (pintype "bidirectional"))
      (node (ref "IC15") (pin "P15") (pinfunction "NO1_P15") (pintype "bidirectional"))
      (node (ref "IC15") (pin "P3") (pinfunction "NO2_P3") (pintype "bidirectional"))
      (node (ref "IC16") (pin "P15") (pinfunction "NO1_P15") (pintype "bidirectional"))
      (node (ref "IC16") (pin "P3") (pinfunction "NO2_P3") (pintype "bidirectional"))
      (node (ref "IC18") (pin "P15") (pinfunction "NO1_P15") (pintype "bidirectional"))
      (node (ref "IC18") (pin "P3") (pinfunction "NO2_P3") (pintype "bidirectional"))
      (node (ref "IC19") (pin "P15") (pinfunction "NO1_P15") (pintype "bidirectional"))
      (node (ref "IC19") (pin "P3") (pinfunction "NO2_P3") (pintype "bidirectional"))
      (node (ref "J1") (pin "P2") (pinfunction "2_P2") (pintype "passive"))
    )
    (net (code "39") (name "Net-(IC1-VBUS)") (class "Default")
      (node (ref "C2") (pin "1") (pinfunction "1_1") (pintype "passive"))
      (node (ref "IC1") (pin "P$5") (pinfunction "VBUS_P$5") (pintype "bidirectional"))
      (node (ref "L1") (pin "2") (pinfunction "2_2") (pintype "passive"))
      (node (ref "USB") (pin "P$1") (pinfunction "1_P$1") (pintype "bidirectional"))
    )
    (net (code "40") (name "Net-(IC3-3V3OUT)") (class "Default")
      (node (ref "C8") (pin "1") (pinfunction "1_1") (pintype "passive"))
      (node (ref "IC3") (pin "17") (pinfunction "3V3OUT_17") (pintype "output"))
    )
    (net (code "41") (name "Net-(IC3-CBUS0)") (class "Default")
      (node (ref "IC3") (pin "23") (pinfunction "CBUS0_23") (pintype "bidirectional"))
      (node (ref "TX") (pin "K") (pinfunction "K_K") (pintype "bidirectional"))
    )
    (net (code "42") (name "Net-(IC3-CBUS1)") (class "Default")
      (node (ref "IC3") (pin "22") (pinfunction "CBUS1_22") (pintype "bidirectional"))
      (node (ref "RX") (pin "K") (pinfunction "K_K") (pintype "bidirectional"))
    )
    (net (code "43") (name "Net-(IC4-PR1{slash}XTAL1)") (class "Default")
      (node (ref "IC4") (pin "37") (pinfunction "PR1/XTAL1_37") (pintype "bidirectional"))
      (node (ref "OSC") (pin "P$3") (pinfunction "OUTPUT_P$3") (pintype "passive"))
    )
    (net (code "44") (name "Net-(IC5-P$4)") (class "Default")
      (node (ref "IC5") (pin "4") (pinfunction "P$4_4") (pintype "bidirectional"))
      (node (ref "R4") (pin "1") (pinfunction "1_1") (pintype "passive"))
    )
    (net (code "45") (name "Net-(IC6-P$4)") (class "Default")
      (node (ref "IC6") (pin "4") (pinfunction "P$4_4") (pintype "bidirectional"))
      (node (ref "R10") (pin "1") (pinfunction "1_1") (pintype "passive"))
    )
    (net (code "46") (name "Net-(IC7-P$4)") (class "Default")
      (node (ref "IC7") (pin "4") (pinfunction "P$4_4") (pintype "bidirectional"))
      (node (ref "R11") (pin "1") (pinfunction "1_1") (pintype "passive"))
    )
    (net (code "47") (name "Net-(IC8-P$4)") (class "Default")
      (node (ref "IC8") (pin "4") (pinfunction "P$4_4") (pintype "bidirectional"))
      (node (ref "R12") (pin "1") (pinfunction "1_1") (pintype "passive"))
    )
    (net (code "48") (name "Net-(IC9-P$4)") (class "Default")
      (node (ref "IC9") (pin "4") (pinfunction "P$4_4") (pintype "bidirectional"))
      (node (ref "R13") (pin "1") (pinfunction "1_1") (pintype "passive"))
    )
    (net (code "49") (name "Net-(IC10-P$4)") (class "Default")
      (node (ref "IC10") (pin "4") (pinfunction "P$4_4") (pintype "bidirectional"))
      (node (ref "R14") (pin "1") (pinfunction "1_1") (pintype "passive"))
    )
    (net (code "50") (name "Net-(R1-Pad1)") (class "Default")
      (node (ref "R1") (pin "1") (pinfunction "1_1") (pintype "passive"))
      (node (ref "TX") (pin "A") (pinfunction "A_A") (pintype "bidirectional"))
    )
    (net (code "51") (name "Net-(R2-Pad1)") (class "Default")
      (node (ref "R2") (pin "1") (pinfunction "1_1") (pintype "passive"))
      (node (ref "RX") (pin "A") (pinfunction "A_A") (pintype "bidirectional"))
    )
    (net (code "52") (name "Net-(R3-Pad1)") (class "Default")
      (node (ref "R3") (pin "1") (pinfunction "1_1") (pintype "passive"))
      (node (ref "STATE") (pin "A") (pinfunction "A_A") (pintype "bidirectional"))
    )
    (net (code "53") (name "Net-(USB-2)") (class "Default")
      (node (ref "IC1") (pin "P$1") (pinfunction "IO1_P$1") (pintype "bidirectional"))
      (node (ref "USB") (pin "P$2") (pinfunction "2_P$2") (pintype "bidirectional"))
    )
    (net (code "54") (name "Net-(USB-3)") (class "Default")
      (node (ref "IC1") (pin "P$3") (pinfunction "IO2_P$3") (pintype "bidirectional"))
      (node (ref "USB") (pin "P$3") (pinfunction "3_P$3") (pintype "bidirectional"))
    )
    (net (code "55") (name "Net-(USB-P$1)") (class "Default")
      (node (ref "RUSB") (pin "1") (pinfunction "1_1") (pintype "passive"))
      (node (ref "USB") (pin "SHIELD_1") (pinfunction "P$1_SHIELD_1") (pintype "bidirectional"))
    )
    (net (code "56") (name "Net-(USB-P$4)") (class "Default")
      (node (ref "CUSB") (pin "1") (pinfunction "1_1") (pintype "passive"))
      (node (ref "USB") (pin "SHIELD_4") (pinfunction "P$4_SHIELD_4") (pintype "bidirectional"))
    )
    (net (code "57") (name "OUT0") (class "Default")
      (node (ref "IC4") (pin "11") (pinfunction "PC1/OC0B/XCK0/SCL_11") (pintype "bidirectional"))
      (node (ref "IC5") (pin "2") (pinfunction "P$2_2") (pintype "bidirectional"))
    )
    (net (code "58") (name "OUT_SPK0_N") (class "Default")
      (node (ref "IC11") (pin "P8") (pinfunction "COM3_P8") (pintype "bidirectional"))
      (node (ref "X7") (pin "P4") (pinfunction "4_P4") (pintype "passive"))
    )
    (net (code "59") (name "OUT_SPK0_P") (class "Default")
      (node (ref "IC11") (pin "P16") (pinfunction "COM1_P16") (pintype "bidirectional"))
      (node (ref "X7") (pin "P3") (pinfunction "3_P3") (pintype "passive"))
    )
    (net (code "60") (name "OUT_SPK1_N") (class "Default")
      (node (ref "IC11") (pin "P12") (pinfunction "COM4_P12") (pintype "bidirectional"))
      (node (ref "X7") (pin "P2") (pinfunction "2_P2") (pintype "passive"))
    )
    (net (code "61") (name "OUT_SPK1_P") (class "Default")
      (node (ref "IC11") (pin "P4") (pinfunction "COM2_P4") (pintype "bidirectional"))
      (node (ref "X7") (pin "P1") (pinfunction "1_P1") (pintype "passive"))
    )
    (net (code "62") (name "OUT_SPK2_N") (class "Default")
      (node (ref "IC13") (pin "P8") (pinfunction "COM3_P8") (pintype "bidirectional"))
      (node (ref "X6") (pin "P8") (pinfunction "8_P8") (pintype "passive"))
    )
    (net (code "63") (name "OUT_SPK2_P") (class "Default")
      (node (ref "IC13") (pin "P16") (pinfunction "COM1_P16") (pintype "bidirectional"))
      (node (ref "X6") (pin "P7") (pinfunction "7_P7") (pintype "passive"))
    )
    (net (code "64") (name "OUT_SPK3_N") (class "Default")
      (node (ref "IC13") (pin "P12") (pinfunction "COM4_P12") (pintype "bidirectional"))
      (node (ref "X6") (pin "P6") (pinfunction "6_P6") (pintype "passive"))
    )
    (net (code "65") (name "OUT_SPK3_P") (class "Default")
      (node (ref "IC13") (pin "P4") (pinfunction "COM2_P4") (pintype "bidirectional"))
      (node (ref "X6") (pin "P5") (pinfunction "5_P5") (pintype "passive"))
    )
    (net (code "66") (name "OUT_SPK4_N") (class "Default")
      (node (ref "IC15") (pin "P8") (pinfunction "COM3_P8") (pintype "bidirectional"))
      (node (ref "X6") (pin "P4") (pinfunction "4_P4") (pintype "passive"))
    )
    (net (code "67") (name "OUT_SPK4_P") (class "Default")
      (node (ref "IC15") (pin "P16") (pinfunction "COM1_P16") (pintype "bidirectional"))
      (node (ref "X6") (pin "P3") (pinfunction "3_P3") (pintype "passive"))
    )
    (net (code "68") (name "OUT_SPK5_N") (class "Default")
      (node (ref "IC15") (pin "P12") (pinfunction "COM4_P12") (pintype "bidirectional"))
      (node (ref "X6") (pin "P2") (pinfunction "2_P2") (pintype "passive"))
    )
    (net (code "69") (name "OUT_SPK5_P") (class "Default")
      (node (ref "IC15") (pin "P4") (pinfunction "COM2_P4") (pintype "bidirectional"))
      (node (ref "X6") (pin "P1") (pinfunction "1_P1") (pintype "passive"))
    )
    (net (code "70") (name "OUT_SPK6_N") (class "Default")
      (node (ref "IC18") (pin "P8") (pinfunction "COM3_P8") (pintype "bidirectional"))
      (node (ref "X5") (pin "P4") (pinfunction "4_P4") (pintype "passive"))
    )
    (net (code "71") (name "OUT_SPK6_P") (class "Default")
      (node (ref "IC18") (pin "P16") (pinfunction "COM1_P16") (pintype "bidirectional"))
      (node (ref "X5") (pin "P3") (pinfunction "3_P3") (pintype "passive"))
    )
    (net (code "72") (name "OUT_SPK7_N") (class "Default")
      (node (ref "IC18") (pin "P12") (pinfunction "COM4_P12") (pintype "bidirectional"))
      (node (ref "X5") (pin "P2") (pinfunction "2_P2") (pintype "passive"))
    )
    (net (code "73") (name "OUT_SPK7_P") (class "Default")
      (node (ref "IC18") (pin "P4") (pinfunction "COM2_P4") (pintype "bidirectional"))
      (node (ref "X5") (pin "P1") (pinfunction "1_P1") (pintype "passive"))
    )
    (net (code "74") (name "OUT_SPK8_N") (class "Default")
      (node (ref "IC12") (pin "P8") (pinfunction "COM3_P8") (pintype "bidirectional"))
      (node (ref "X4") (pin "P8") (pinfunction "8_P8") (pintype "passive"))
    )
    (net (code "75") (name "OUT_SPK8_P") (class "Default")
      (node (ref "IC12") (pin "P16") (pinfunction "COM1_P16") (pintype "bidirectional"))
      (node (ref "X4") (pin "P7") (pinfunction "7_P7") (pintype "passive"))
    )
    (net (code "76") (name "OUT_SPK9_N") (class "Default")
      (node (ref "IC12") (pin "P12") (pinfunction "COM4_P12") (pintype "bidirectional"))
      (node (ref "X4") (pin "P6") (pinfunction "6_P6") (pintype "passive"))
    )
    (net (code "77") (name "OUT_SPK9_P") (class "Default")
      (node (ref "IC12") (pin "P4") (pinfunction "COM2_P4") (pintype "bidirectional"))
      (node (ref "X4") (pin "P5") (pinfunction "5_P5") (pintype "passive"))
    )
    (net (code "78") (name "OUT_SPK10_N") (class "Default")
      (node (ref "IC14") (pin "P8") (pinfunction "COM3_P8") (pintype "bidirectional"))
      (node (ref "X4") (pin "P4") (pinfunction "4_P4") (pintype "passive"))
    )
    (net (code "79") (name "OUT_SPK10_P") (class "Default")
      (node (ref "IC14") (pin "P16") (pinfunction "COM1_P16") (pintype "bidirectional"))
      (node (ref "X4") (pin "P3") (pinfunction "3_P3") (pintype "passive"))
    )
    (net (code "80") (name "OUT_SPK11_N") (class "Default")
      (node (ref "IC14") (pin "P12") (pinfunction "COM4_P12") (pintype "bidirectional"))
      (node (ref "X4") (pin "P2") (pinfunction "2_P2") (pintype "passive"))
    )
    (net (code "81") (name "OUT_SPK11_P") (class "Default")
      (node (ref "IC14") (pin "P4") (pinfunction "COM2_P4") (pintype "bidirectional"))
      (node (ref "X4") (pin "P1") (pinfunction "1_P1") (pintype "passive"))
    )
    (net (code "82") (name "OUT_SPK12_N") (class "Default")
      (node (ref "IC16") (pin "P8") (pinfunction "COM3_P8") (pintype "bidirectional"))
      (node (ref "X3") (pin "P8") (pinfunction "8_P8") (pintype "passive"))
    )
    (net (code "83") (name "OUT_SPK12_P") (class "Default")
      (node (ref "IC16") (pin "P16") (pinfunction "COM1_P16") (pintype "bidirectional"))
      (node (ref "X3") (pin "P7") (pinfunction "7_P7") (pintype "passive"))
    )
    (net (code "84") (name "OUT_SPK13_N") (class "Default")
      (node (ref "IC16") (pin "P12") (pinfunction "COM4_P12") (pintype "bidirectional"))
      (node (ref "X3") (pin "P6") (pinfunction "6_P6") (pintype "passive"))
    )
    (net (code "85") (name "OUT_SPK13_P") (class "Default")
      (node (ref "IC16") (pin "P4") (pinfunction "COM2_P4") (pintype "bidirectional"))
      (node (ref "X3") (pin "P5") (pinfunction "5_P5") (pintype "passive"))
    )
    (net (code "86") (name "OUT_SPK14_N") (class "Default")
      (node (ref "IC19") (pin "P8") (pinfunction "COM3_P8") (pintype "bidirectional"))
      (node (ref "X3") (pin "P4") (pinfunction "4_P4") (pintype "passive"))
    )
    (net (code "87") (name "OUT_SPK14_P") (class "Default")
      (node (ref "IC19") (pin "P16") (pinfunction "COM1_P16") (pintype "bidirectional"))
      (node (ref "X3") (pin "P3") (pinfunction "3_P3") (pintype "passive"))
    )
    (net (code "88") (name "OUT_SPK15_N") (class "Default")
      (node (ref "IC19") (pin "P12") (pinfunction "COM4_P12") (pintype "bidirectional"))
      (node (ref "X3") (pin "P2") (pinfunction "2_P2") (pintype "passive"))
    )
    (net (code "89") (name "OUT_SPK15_P") (class "Default")
      (node (ref "IC19") (pin "P4") (pinfunction "COM2_P4") (pintype "bidirectional"))
      (node (ref "X3") (pin "P1") (pinfunction "1_P1") (pintype "passive"))
    )
    (net (code "90") (name "PDI-CLK") (class "Default")
      (node (ref "IC4") (pin "35") (pinfunction "RESET/PDI-CLK_35") (pintype "input"))
      (node (ref "PDI") (pin "5") (pinfunction "5_5") (pintype "passive"))
    )
    (net (code "91") (name "PDI-DATA") (class "Default")
      (node (ref "IC4") (pin "34") (pinfunction "PDI-DATA_34") (pintype "bidirectional"))
      (node (ref "PDI") (pin "1") (pinfunction "1_1") (pintype "passive"))
    )
    (net (code "92") (name "STATE") (class "Default")
      (node (ref "IC4") (pin "36") (pinfunction "PR0/XTAL2_36") (pintype "bidirectional"))
      (node (ref "R3") (pin "2") (pinfunction "2_2") (pintype "passive"))
    )
    (net (code "93") (name "USBDM") (class "Default")
      (node (ref "C4") (pin "1") (pinfunction "1_1") (pintype "passive"))
      (node (ref "IC1") (pin "P$6") (pinfunction "IO1_P$6") (pintype "bidirectional"))
      (node (ref "IC3") (pin "16") (pinfunction "USBDM_16") (pintype "bidirectional"))
    )
    (net (code "94") (name "USBDP") (class "Default")
      (node (ref "C3") (pin "1") (pinfunction "1_1") (pintype "passive"))
      (node (ref "IC1") (pin "P$4") (pinfunction "IO2_P$4") (pintype "bidirectional"))
      (node (ref "IC3") (pin "15") (pinfunction "USBDP_15") (pintype "bidirectional"))
    )
    (net (code "95") (name "VCC") (class "Default")
      (node (ref "C22") (pin "1") (pinfunction "1_1") (pintype "passive"))
      (node (ref "C23") (pin "1") (pinfunction "1_1") (pintype "passive"))
      (node (ref "C24") (pin "1") (pinfunction "1_1") (pintype "passive"))
      (node (ref "C25") (pin "1") (pinfunction "1_1") (pintype "passive"))
      (node (ref "C26") (pin "1") (pinfunction "1_1") (pintype "passive"))
      (node (ref "C27") (pin "1") (pinfunction "1_1") (pintype "passive"))
      (node (ref "C29") (pin "1") (pinfunction "1_1") (pintype "passive"))
      (node (ref "C30") (pin "1") (pinfunction "1_1") (pintype "passive"))
      (node (ref "C31") (pin "1") (pinfunction "1_1") (pintype "passive"))
      (node (ref "D1") (pin "A") (pinfunction "A_A") (pintype "passive"))
      (node (ref "IC11") (pin "P14") (pinfunction "VCC_P14") (pintype "bidirectional"))
      (node (ref "IC12") (pin "P14") (pinfunction "VCC_P14") (pintype "bidirectional"))
      (node (ref "IC13") (pin "P14") (pinfunction "VCC_P14") (pintype "bidirectional"))
      (node (ref "IC14") (pin "P14") (pinfunction "VCC_P14") (pintype "bidirectional"))
      (node (ref "IC15") (pin "P14") (pinfunction "VCC_P14") (pintype "bidirectional"))
      (node (ref "IC16") (pin "P14") (pinfunction "VCC_P14") (pintype "bidirectional"))
      (node (ref "IC17") (pin "5") (pinfunction "OUT_5") (pintype "bidirectional"))
      (node (ref "IC18") (pin "P14") (pinfunction "VCC_P14") (pintype "bidirectional"))
      (node (ref "IC19") (pin "P14") (pinfunction "VCC_P14") (pintype "bidirectional"))
    )
    (net (code "96") (name "VCCIO") (class "Default")
      (node (ref "C10") (pin "1") (pinfunction "1_1") (pintype "passive"))
      (node (ref "C11") (pin "1") (pinfunction "1_1") (pintype "passive"))
      (node (ref "C12") (pin "1") (pinfunction "1_1") (pintype "passive"))
      (node (ref "C13") (pin "1") (pinfunction "1_1") (pintype "passive"))
      (node (ref "C14") (pin "1") (pinfunction "1_1") (pintype "passive"))
      (node (ref "C15") (pin "1") (pinfunction "1_1") (pintype "passive"))
      (node (ref "C17") (pin "1") (pinfunction "1_1") (pintype "passive"))
      (node (ref "C18") (pin "1") (pinfunction "1_1") (pintype "passive"))
      (node (ref "C19") (pin "1") (pinfunction "1_1") (pintype "passive"))
      (node (ref "C20") (pin "1") (pinfunction "1_1") (pintype "passive"))
      (node (ref "C21") (pin "1") (pinfunction "1_1") (pintype "passive"))
      (node (ref "C9") (pin "1") (pinfunction "1_1") (pintype "passive"))
      (node (ref "CLKIN") (pin "1") (pinfunction "1_1") (pintype "passive"))
      (node (ref "D1") (pin "C") (pinfunction "C_C") (pintype "passive"))
      (node (ref "IC10") (pin "5") (pinfunction "P$5_5") (pintype "bidirectional"))
      (node (ref "IC2") (pin "5") (pinfunction "OUT_5") (pintype "bidirectional"))
      (node (ref "IC3") (pin "4") (pinfunction "VCCIO_4") (pintype "power_in"))
      (node (ref "IC4") (pin "19") (pinfunction "VCC_19") (pintype "power_in"))
      (node (ref "IC4") (pin "31") (pinfunction "VCC_31") (pintype "power_in"))
      (node (ref "IC4") (pin "39") (pinfunction "AVCC_39") (pintype "power_in"))
      (node (ref "IC4") (pin "9") (pinfunction "VCC_9") (pintype "power_in"))
      (node (ref "IC6") (pin "5") (pinfunction "P$5_5") (pintype "bidirectional"))
      (node (ref "IC7") (pin "5") (pinfunction "P$5_5") (pintype "bidirectional"))
      (node (ref "IC8") (pin "5") (pinfunction "P$5_5") (pintype "bidirectional"))
      (node (ref "IC9") (pin "5") (pinfunction "P$5_5") (pintype "bidirectional"))
      (node (ref "JP1") (pin "1") (pinfunction "1_1") (pintype "passive"))
      (node (ref "JP2") (pin "1") (pinfunction "1_1") (pintype "passive"))
      (node (ref "OSC") (pin "P$4") (pinfunction "VDD_P$4") (pintype "passive"))
      (node (ref "PDI") (pin "2") (pinfunction "2_2") (pintype "passive"))
    )
    (net (code "97") (name "VDD_OUT") (class "Default")
      (node (ref "C16") (pin "1") (pinfunction "1_1") (pintype "passive"))
      (node (ref "IC5") (pin "5") (pinfunction "P$5_5") (pintype "bidirectional"))
      (node (ref "JP1") (pin "2") (pinfunction "2_2") (pintype "passive"))
    )
    (net (code "98") (name "unconnected-(IC2-N{slash}C-Pad4)") (class "Default")
      (node (ref "IC2") (pin "4") (pinfunction "N/C_4") (pintype "bidirectional"))
    )
    (net (code "99") (name "unconnected-(IC3-CBUS2-Pad13)") (class "Default")
      (node (ref "IC3") (pin "13") (pinfunction "CBUS2_13") (pintype "bidirectional"))
    )
    (net (code "100") (name "unconnected-(IC3-CBUS3-Pad14)") (class "Default")
      (node (ref "IC3") (pin "14") (pinfunction "CBUS3_14") (pintype "bidirectional"))
    )
    (net (code "101") (name "unconnected-(IC3-CBUS4-Pad12)") (class "Default")
      (node (ref "IC3") (pin "12") (pinfunction "CBUS4_12") (pintype "bidirectional"))
    )
    (net (code "102") (name "unconnected-(IC3-OSCI-Pad27)") (class "Default")
      (node (ref "IC3") (pin "27") (pinfunction "OSCI_27") (pintype "input"))
    )
    (net (code "103") (name "unconnected-(IC3-OSCO-Pad28)") (class "Default")
      (node (ref "IC3") (pin "28") (pinfunction "OSCO_28") (pintype "output"))
    )
    (net (code "104") (name "unconnected-(IC3-~{DCD}-Pad10)") (class "Default")
      (node (ref "IC3") (pin "10") (pinfunction "~{DCD}_10") (pintype "input"))
    )
    (net (code "105") (name "unconnected-(IC3-~{DSR}-Pad9)") (class "Default")
      (node (ref "IC3") (pin "9") (pinfunction "~{DSR}_9") (pintype "input"))
    )
    (net (code "106") (name "unconnected-(IC3-~{DTR}-Pad2)") (class "Default")
      (node (ref "IC3") (pin "2") (pinfunction "~{DTR}_2") (pintype "output"))
    )
    (net (code "107") (name "unconnected-(IC3-~{RESET}-Pad19)") (class "Default")
      (node (ref "IC3") (pin "19") (pinfunction "~{RESET}_19") (pintype "input"))
    )
    (net (code "108") (name "unconnected-(IC3-~{RI}-Pad6)") (class "Default")
      (node (ref "IC3") (pin "6") (pinfunction "~{RI}_6") (pintype "input"))
    )
    (net (code "109") (name "unconnected-(IC4-PC3{slash}OC0D{slash}TXD0-Pad13)") (class "Default")
      (node (ref "IC4") (pin "13") (pinfunction "PC3/OC0D/TXD0_13") (pintype "bidirectional"))
    )
    (net (code "110") (name "unconnected-(IC4-PC5{slash}OC1B{slash}MOSI{slash}XCK1-Pad15)") (class "Default")
      (node (ref "IC4") (pin "15") (pinfunction "PC5/OC1B/MOSI/XCK1_15") (pintype "bidirectional"))
    )
    (net (code "111") (name "unconnected-(IC4-PC6{slash}MISO{slash}RXD1-Pad16)") (class "Default")
      (node (ref "IC4") (pin "16") (pinfunction "PC6/MISO/RXD1_16") (pintype "bidirectional"))
    )
    (net (code "112") (name "unconnected-(IC4-PC7{slash}SCK{slash}TXD1{slash}CLKO{slash}EVO-Pad17)") (class "Default")
      (node (ref "IC4") (pin "17") (pinfunction "PC7/SCK/TXD1/CLKO/EVO_17") (pintype "bidirectional"))
    )
    (net (code "113") (name "unconnected-(IC11-NC1-PadP1)") (class "Default")
      (node (ref "IC11") (pin "P1") (pinfunction "NC1_P1") (pintype "bidirectional"))
    )
    (net (code "114") (name "unconnected-(IC11-NC2-PadP5)") (class "Default")
      (node (ref "IC11") (pin "P5") (pinfunction "NC2_P5") (pintype "bidirectional"))
    )
    (net (code "115") (name "unconnected-(IC11-NC3-PadP9)") (class "Default")
      (node (ref "IC11") (pin "P9") (pinfunction "NC3_P9") (pintype "power_in"))
    )
    (net (code "116") (name "unconnected-(IC11-NC4-PadP13)") (class "Default")
      (node (ref "IC11") (pin "P13") (pinfunction "NC4_P13") (pintype "bidirectional"))
    )
    (net (code "117") (name "unconnected-(IC12-NC1-PadP1)") (class "Default")
      (node (ref "IC12") (pin "P1") (pinfunction "NC1_P1") (pintype "bidirectional"))
    )
    (net (code "118") (name "unconnected-(IC12-NC2-PadP5)") (class "Default")
      (node (ref "IC12") (pin "P5") (pinfunction "NC2_P5") (pintype "bidirectional"))
    )
    (net (code "119") (name "unconnected-(IC12-NC3-PadP9)") (class "Default")
      (node (ref "IC12") (pin "P9") (pinfunction "NC3_P9") (pintype "power_in"))
    )
    (net (code "120") (name "unconnected-(IC12-NC4-PadP13)") (class "Default")
      (node (ref "IC12") (pin "P13") (pinfunction "NC4_P13") (pintype "bidirectional"))
    )
    (net (code "121") (name "unconnected-(IC13-NC1-PadP1)") (class "Default")
      (node (ref "IC13") (pin "P1") (pinfunction "NC1_P1") (pintype "bidirectional"))
    )
    (net (code "122") (name "unconnected-(IC13-NC2-PadP5)") (class "Default")
      (node (ref "IC13") (pin "P5") (pinfunction "NC2_P5") (pintype "bidirectional"))
    )
    (net (code "123") (name "unconnected-(IC13-NC3-PadP9)") (class "Default")
      (node (ref "IC13") (pin "P9") (pinfunction "NC3_P9") (pintype "power_in"))
    )
    (net (code "124") (name "unconnected-(IC13-NC4-PadP13)") (class "Default")
      (node (ref "IC13") (pin "P13") (pinfunction "NC4_P13") (pintype "bidirectional"))
    )
    (net (code "125") (name "unconnected-(IC14-NC1-PadP1)") (class "Default")
      (node (ref "IC14") (pin "P1") (pinfunction "NC1_P1") (pintype "bidirectional"))
    )
    (net (code "126") (name "unconnected-(IC14-NC2-PadP5)") (class "Default")
      (node (ref "IC14") (pin "P5") (pinfunction "NC2_P5") (pintype "bidirectional"))
    )
    (net (code "127") (name "unconnected-(IC14-NC3-PadP9)") (class "Default")
      (node (ref "IC14") (pin "P9") (pinfunction "NC3_P9") (pintype "power_in"))
    )
    (net (code "128") (name "unconnected-(IC14-NC4-PadP13)") (class "Default")
      (node (ref "IC14") (pin "P13") (pinfunction "NC4_P13") (pintype "bidirectional"))
    )
    (net (code "129") (name "unconnected-(IC15-NC1-PadP1)") (class "Default")
      (node (ref "IC15") (pin "P1") (pinfunction "NC1_P1") (pintype "bidirectional"))
    )
    (net (code "130") (name "unconnected-(IC15-NC2-PadP5)") (class "Default")
      (node (ref "IC15") (pin "P5") (pinfunction "NC2_P5") (pintype "bidirectional"))
    )
    (net (code "131") (name "unconnected-(IC15-NC3-PadP9)") (class "Default")
      (node (ref "IC15") (pin "P9") (pinfunction "NC3_P9") (pintype "power_in"))
    )
    (net (code "132") (name "unconnected-(IC15-NC4-PadP13)") (class "Default")
      (node (ref "IC15") (pin "P13") (pinfunction "NC4_P13") (pintype "bidirectional"))
    )
    (net (code "133") (name "unconnected-(IC16-NC1-PadP1)") (class "Default")
      (node (ref "IC16") (pin "P1") (pinfunction "NC1_P1") (pintype "bidirectional"))
    )
    (net (code "134") (name "unconnected-(IC16-NC2-PadP5)") (class "Default")
      (node (ref "IC16") (pin "P5") (pinfunction "NC2_P5") (pintype "bidirectional"))
    )
    (net (code "135") (name "unconnected-(IC16-NC3-PadP9)") (class "Default")
      (node (ref "IC16") (pin "P9") (pinfunction "NC3_P9") (pintype "power_in"))
    )
    (net (code "136") (name "unconnected-(IC16-NC4-PadP13)") (class "Default")
      (node (ref "IC16") (pin "P13") (pinfunction "NC4_P13") (pintype "bidirectional"))
    )
    (net (code "137") (name "unconnected-(IC17-N{slash}C-Pad4)") (class "Default")
      (node (ref "IC17") (pin "4") (pinfunction "N/C_4") (pintype "bidirectional"))
    )
    (net (code "138") (name "unconnected-(IC18-NC1-PadP1)") (class "Default")
      (node (ref "IC18") (pin "P1") (pinfunction "NC1_P1") (pintype "bidirectional"))
    )
    (net (code "139") (name "unconnected-(IC18-NC2-PadP5)") (class "Default")
      (node (ref "IC18") (pin "P5") (pinfunction "NC2_P5") (pintype "bidirectional"))
    )
    (net (code "140") (name "unconnected-(IC18-NC3-PadP9)") (class "Default")
      (node (ref "IC18") (pin "P9") (pinfunction "NC3_P9") (pintype "power_in"))
    )
    (net (code "141") (name "unconnected-(IC18-NC4-PadP13)") (class "Default")
      (node (ref "IC18") (pin "P13") (pinfunction "NC4_P13") (pintype "bidirectional"))
    )
    (net (code "142") (name "unconnected-(IC19-NC1-PadP1)") (class "Default")
      (node (ref "IC19") (pin "P1") (pinfunction "NC1_P1") (pintype "bidirectional"))
    )
    (net (code "143") (name "unconnected-(IC19-NC2-PadP5)") (class "Default")
      (node (ref "IC19") (pin "P5") (pinfunction "NC2_P5") (pintype "bidirectional"))
    )
    (net (code "144") (name "unconnected-(IC19-NC3-PadP9)") (class "Default")
      (node (ref "IC19") (pin "P9") (pinfunction "NC3_P9") (pintype "power_in"))
    )
    (net (code "145") (name "unconnected-(IC19-NC4-PadP13)") (class "Default")
      (node (ref "IC19") (pin "P13") (pinfunction "NC4_P13") (pintype "bidirectional"))
    )
    (net (code "146") (name "unconnected-(J1-3-PadP3)") (class "Default")
      (node (ref "J1") (pin "P3") (pinfunction "3_P3") (pintype "passive"))
    )
    (net (code "147") (name "unconnected-(OSC-STANDBY#-PadP$1)") (class "Default")
      (node (ref "OSC") (pin "P$1") (pinfunction "STANDBY#_P$1") (pintype "passive"))
    )
    (net (code "148") (name "unconnected-(PDI-Pad3)") (class "Default")
      (node (ref "PDI") (pin "3") (pinfunction "3_3") (pintype "passive"))
    )
    (net (code "149") (name "unconnected-(PDI-Pad4)") (class "Default")
      (node (ref "PDI") (pin "4") (pinfunction "4_4") (pintype "passive"))
    )
    (net (code "150") (name "unconnected-(USB-4-PadP$4)") (class "Default")
      (node (ref "USB") (pin "P$4") (pinfunction "4_P$4") (pintype "bidirectional"))
    )
    (net (code "151") (name "unconnected-(USB-P$2-PadSHIELD_2)") (class "Default")
      (node (ref "USB") (pin "SHIELD_2") (pinfunction "P$2_SHIELD_2") (pintype "bidirectional"))
    )
    (net (code "152") (name "unconnected-(USB-P$3-PadSHIELD_3)") (class "Default")
      (node (ref "USB") (pin "SHIELD_3") (pinfunction "P$3_SHIELD_3") (pintype "bidirectional"))
    )
  )
)
